# AMC_SATA_Adapter.net
KiCad netlist of a schematic drawn in Altium Designer
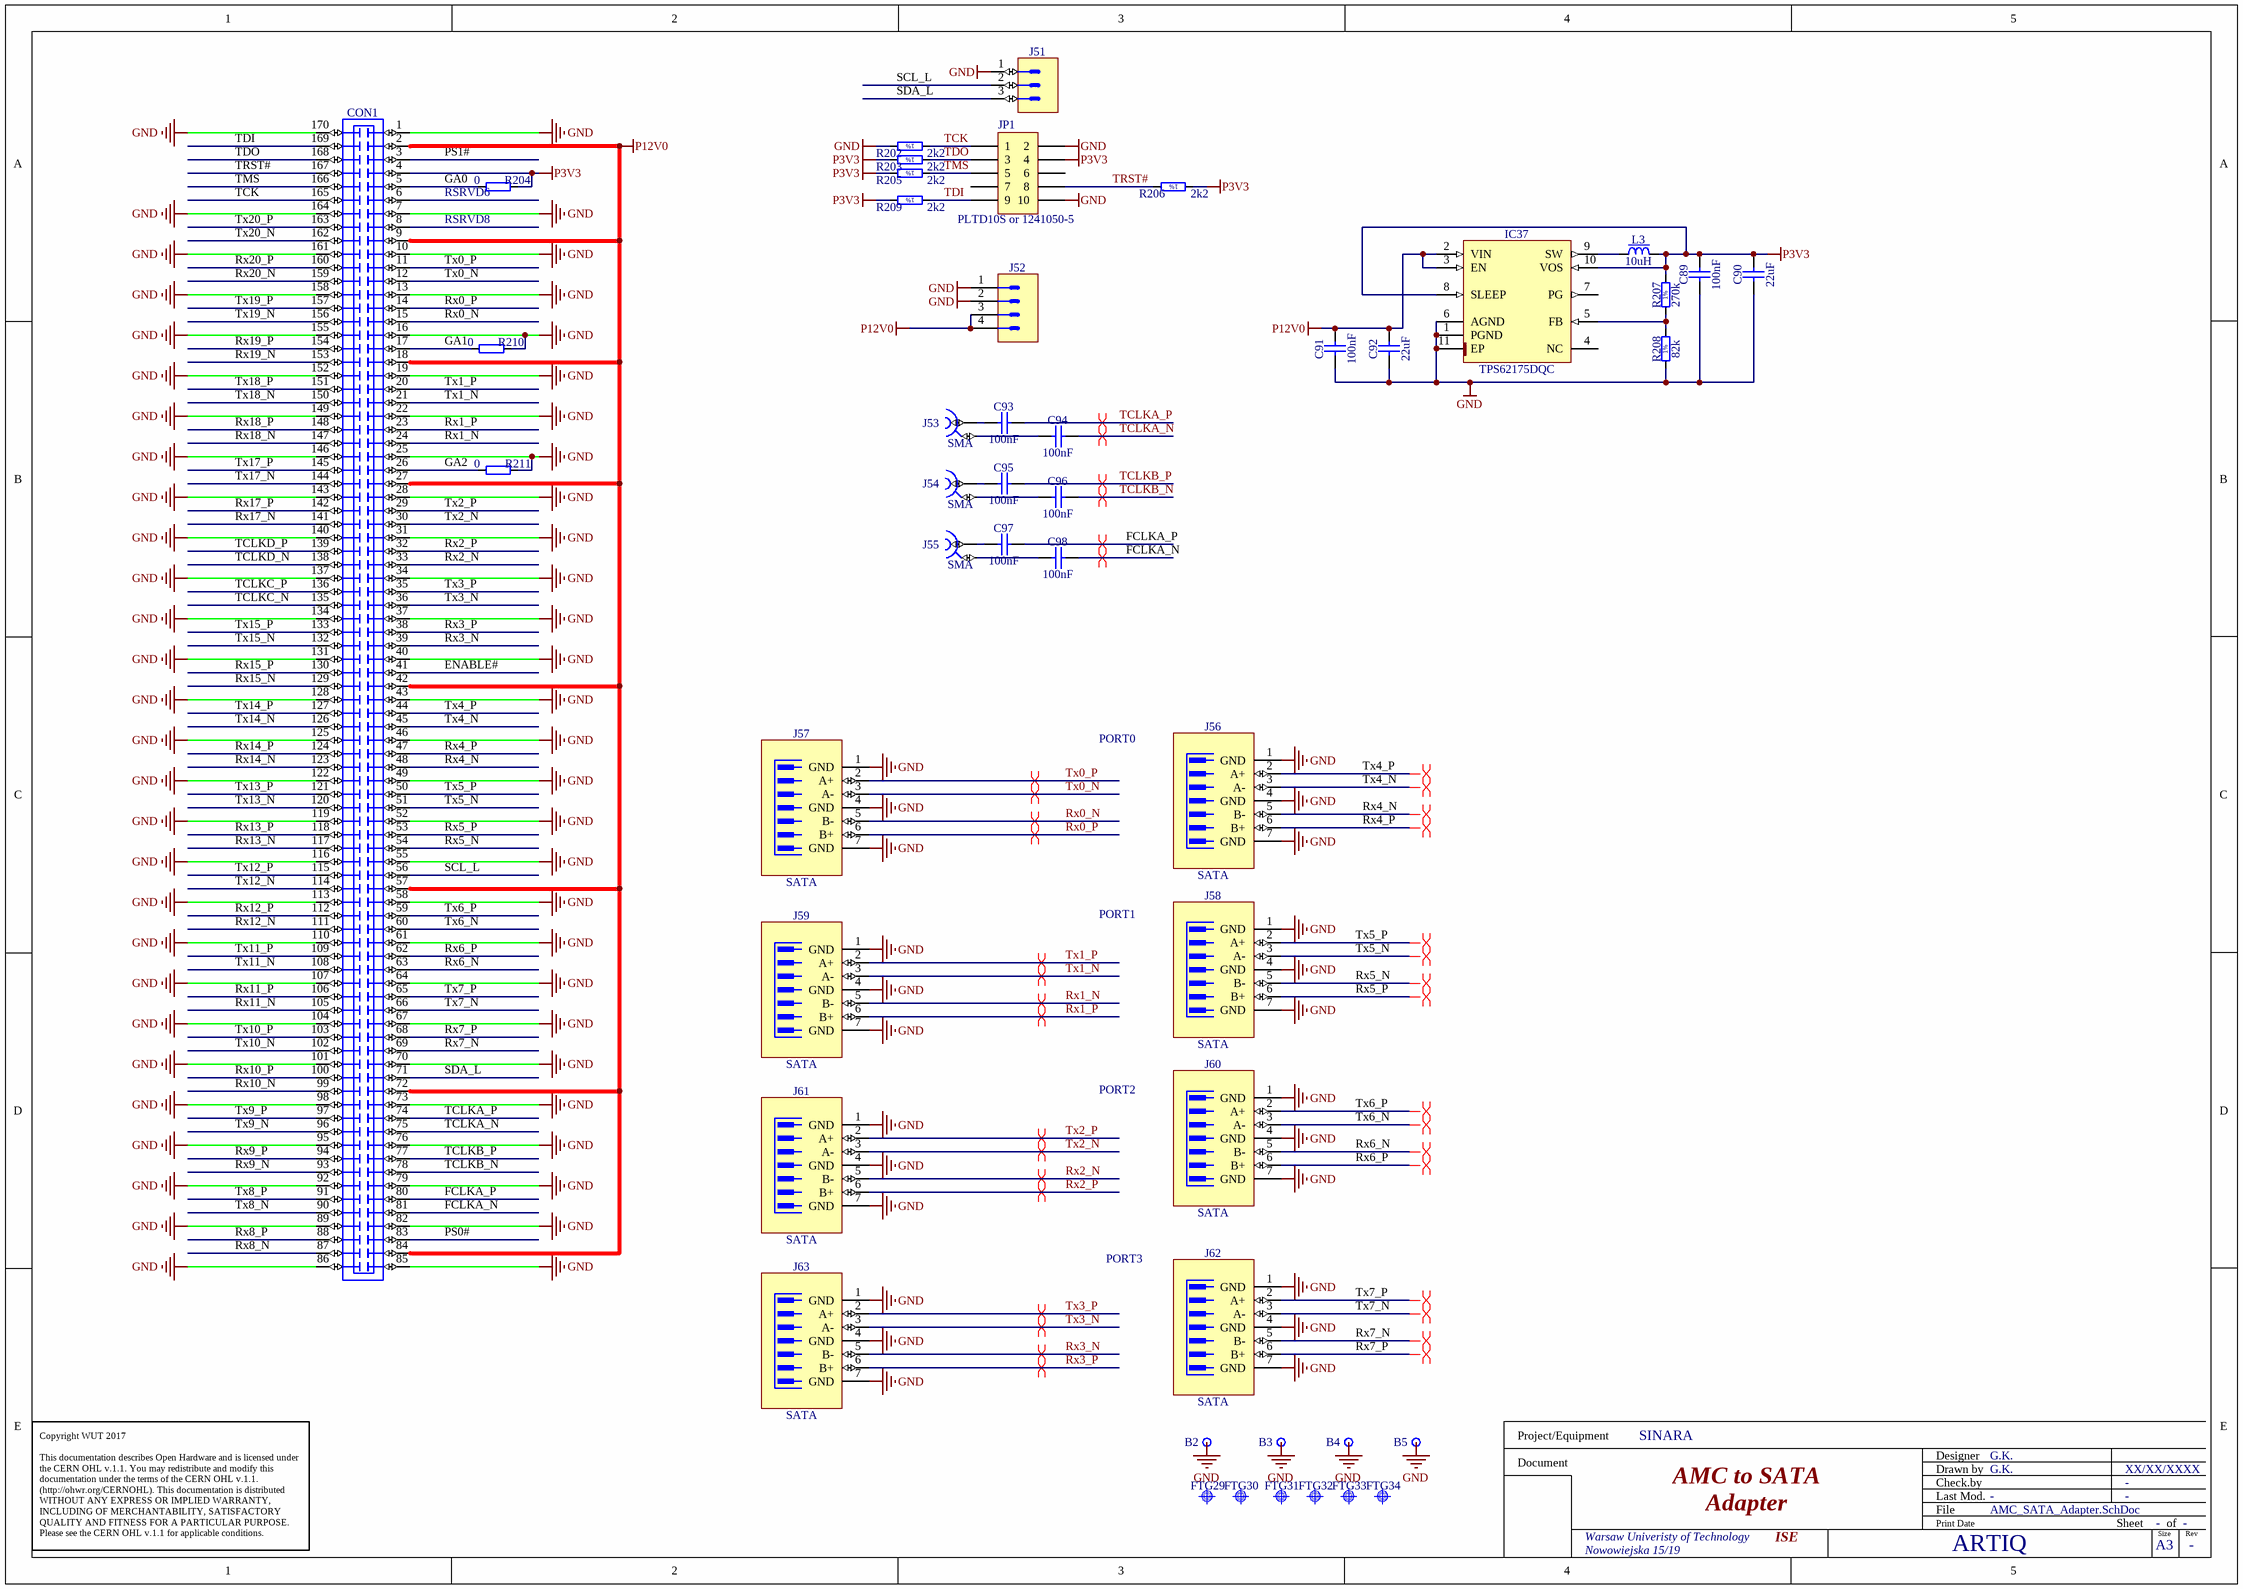
[diagram p0: AMC_SATA_Adapter.SchDoc]

(export (version "E")
  (design (tool "Eeschema 10.0.6"))
  (components
    (comp (ref "B2")
      (value "~")
      (footprint "MTG270_500")
      (description "Through Hole Pad")
      (libsource (lib "Pads") (part "Through Hole Pad"))
    )
    (comp (ref "B3")
      (value "~")
      (footprint "MTG270_500")
      (description "Through Hole Pad")
      (libsource (lib "Pads") (part "Through Hole Pad"))
    )
    (comp (ref "B4")
      (value "~")
      (footprint "MTG270_500")
      (description "Through Hole Pad")
      (libsource (lib "Pads") (part "Through Hole Pad"))
    )
    (comp (ref "B5")
      (value "~")
      (footprint "MTG270_500")
      (description "Through Hole Pad")
      (libsource (lib "Pads") (part "Through Hole Pad"))
    )
    (comp (ref "C89")
      (value "100nF")
      (footprint "CAPC1005X55N")
      (description "Non-polarised capacitor")
      (fields
        (field (name "PART NUMBER") "CC0402_100NF_16V_10%_X5R")
        (field (name "VOLTAGE") "16V")
        (field (name "AUTHOR") "CERN DEM JLC")
      )
      (libsource (lib "Capacitors") (part "Capacitor - non polarized"))
    )
    (comp (ref "C90")
      (value "22uF")
      (footprint "CAPC2012X135N")
      (description "Non-polarised capacitor")
      (fields
        (field (name "PART NUMBER") "CC0805_22UF_16V_10%_X5R")
        (field (name "VOLTAGE") "16V")
        (field (name "AUTHOR") "CERN DEM JLC")
      )
      (libsource (lib "Capacitors") (part "Capacitor - non polarized"))
    )
    (comp (ref "C91")
      (value "100nF")
      (footprint "CAPC1005X55N")
      (description "Non-polarised capacitor")
      (fields
        (field (name "PART NUMBER") "CC0402_100NF_16V_10%_X5R")
        (field (name "VOLTAGE") "16V")
        (field (name "AUTHOR") "CERN DEM JLC")
      )
      (libsource (lib "Capacitors") (part "Capacitor - non polarized"))
    )
    (comp (ref "C92")
      (value "22uF")
      (footprint "CAPC2012X135N")
      (description "Non-polarised capacitor")
      (fields
        (field (name "PART NUMBER") "CC0805_22UF_16V_10%_X5R")
        (field (name "VOLTAGE") "16V")
        (field (name "AUTHOR") "CERN DEM JLC")
      )
      (libsource (lib "Capacitors") (part "Capacitor - non polarized"))
    )
    (comp (ref "C93")
      (value "100nF")
      (footprint "CAPC0603X33N")
      (description "Non-polarised capacitor")
      (fields
        (field (name "PART NUMBER") "CC0201_100NF_6.3V_10%_X5R")
        (field (name "VOLTAGE") "6.3V")
        (field (name "AUTHOR") "CERN DEM JLC")
      )
      (libsource (lib "Capacitors") (part "Capacitor - non polarized"))
    )
    (comp (ref "C94")
      (value "100nF")
      (footprint "CAPC0603X33N")
      (description "Non-polarised capacitor")
      (fields
        (field (name "PART NUMBER") "CC0201_100NF_6.3V_10%_X5R")
        (field (name "VOLTAGE") "6.3V")
        (field (name "AUTHOR") "CERN DEM JLC")
      )
      (libsource (lib "Capacitors") (part "Capacitor - non polarized"))
    )
    (comp (ref "C95")
      (value "100nF")
      (footprint "CAPC0603X33N")
      (description "Non-polarised capacitor")
      (fields
        (field (name "PART NUMBER") "CC0201_100NF_6.3V_10%_X5R")
        (field (name "VOLTAGE") "6.3V")
        (field (name "AUTHOR") "CERN DEM JLC")
      )
      (libsource (lib "Capacitors") (part "Capacitor - non polarized"))
    )
    (comp (ref "C96")
      (value "100nF")
      (footprint "CAPC0603X33N")
      (description "Non-polarised capacitor")
      (fields
        (field (name "PART NUMBER") "CC0201_100NF_6.3V_10%_X5R")
        (field (name "VOLTAGE") "6.3V")
        (field (name "AUTHOR") "CERN DEM JLC")
      )
      (libsource (lib "Capacitors") (part "Capacitor - non polarized"))
    )
    (comp (ref "C97")
      (value "100nF")
      (footprint "CAPC0603X33N")
      (description "Non-polarised capacitor")
      (fields
        (field (name "PART NUMBER") "CC0201_100NF_6.3V_10%_X5R")
        (field (name "VOLTAGE") "6.3V")
        (field (name "AUTHOR") "CERN DEM JLC")
      )
      (libsource (lib "Capacitors") (part "Capacitor - non polarized"))
    )
    (comp (ref "C98")
      (value "100nF")
      (footprint "CAPC0603X33N")
      (description "Non-polarised capacitor")
      (fields
        (field (name "PART NUMBER") "CC0201_100NF_6.3V_10%_X5R")
        (field (name "VOLTAGE") "6.3V")
        (field (name "AUTHOR") "CERN DEM JLC")
      )
      (libsource (lib "Capacitors") (part "Capacitor - non polarized"))
    )
    (comp (ref "CON1")
      (value "SAMTEC_MTCA-085-02-S-DV-SMT-K-TR")
      (footprint "SAMTEC_MTCA-085-02-S-DV-SMT-K-TR")
      (description "170 Poles,  Micro TCA (Telecom Computing Architecture) Edge Card Socket")
      (fields
        (field (name "MANUFACTURER") "SAMTEC")
        (field (name "MANUFACTURER PART NUMBER") "MTCA-085-02-S-DV-SMT-K-TR")
        (field (name "AUTHOR") "CERN DEM JLC")
      )
      (libsource (lib "Connectors") (part "Micro TCA Female 170"))
    )
    (comp (ref "FTG29")
      (value "Use only in PCB")
      (description "Fiducial Target")
      (libsource (lib "Pads") (part "Fiducial Target"))
    )
    (comp (ref "FTG30")
      (value "Use only in PCB")
      (description "Fiducial Target")
      (libsource (lib "Pads") (part "Fiducial Target"))
    )
    (comp (ref "FTG31")
      (value "Use only in PCB")
      (description "Fiducial Target")
      (libsource (lib "Pads") (part "Fiducial Target"))
    )
    (comp (ref "FTG32")
      (value "Use only in PCB")
      (description "Fiducial Target")
      (libsource (lib "Pads") (part "Fiducial Target"))
    )
    (comp (ref "FTG33")
      (value "Use only in PCB")
      (description "Fiducial Target")
      (libsource (lib "Pads") (part "Fiducial Target"))
    )
    (comp (ref "FTG34")
      (value "Use only in PCB")
      (description "Fiducial Target")
      (libsource (lib "Pads") (part "Fiducial Target"))
    )
    (comp (ref "IC37")
      (value "TPS62175DQC")
      (footprint "SON50P200X300X80-11N-R94X250")
      (description "4.75-28VDC to 1-6VDC, 500mA Step-Down Converter With Sleep Mode")
      (fields (field (name "MANUFACTURER") "TEXAS INSTRUMENTS") (field (name "AUTHOR") "CERN DEM JMW"))
      (libsource (lib "ICs And Semiconductors") (part "TPS62175"))
    )
    (comp (ref "J51")
      (value "Header 3")
      (footprint "HARWIN_M22-2010305")
      (description "Connector 3 Male")
      (fields
        (field (name "PART NUMBER") "HARWIN_M22-2010305")
        (field (name "MANUFACTURER") "HARWIN")
        (field (name "AUTHOR") "CERN DEM JLC")
      )
      (libsource (lib "Connectors") (part "Connector 3 Male"))
    )
    (comp (ref "J52")
      (value "Mini-Fit Jr.™")
      (footprint "MOLEX_39-28-1043")
      (description "Connector 4 Male")
      (fields
        (field (name "PART NUMBER") "MOLEX_39-28-1043")
        (field (name "MANUFACTURER") "MOLEX")
        (field (name "AUTHOR") "CERN DEM JLC")
      )
      (libsource (lib "Connectors") (part "Connector 4 Male"))
    )
    (comp (ref "J53")
      (value "SMA")
      (footprint "HUBER-SUHNER_82_SMA-50-0-41/133_NE")
      (fields
        (field (name "PART NUMBER") "HUBER-SUHNER_82_SMA-50-0-41/133_NE")
        (field (name "MANUFACTURER") "HUBER+SUHNER")
        (field (name "MANUFACTURER PART NUMBER") "82_SMA-50-0-41/133_NE")
        (field (name "AUTHOR") "CERN DEM JLC")
      )
      (libsource (lib "Connectors") (part "Coax_1Female_1Shield"))
    )
    (comp (ref "J54")
      (value "SMA")
      (footprint "HUBER-SUHNER_82_SMA-50-0-41/133_NE")
      (fields
        (field (name "PART NUMBER") "HUBER-SUHNER_82_SMA-50-0-41/133_NE")
        (field (name "MANUFACTURER") "HUBER+SUHNER")
        (field (name "MANUFACTURER PART NUMBER") "82_SMA-50-0-41/133_NE")
        (field (name "AUTHOR") "CERN DEM JLC")
      )
      (libsource (lib "Connectors") (part "Coax_1Female_1Shield"))
    )
    (comp (ref "J55")
      (value "SMA")
      (footprint "HUBER-SUHNER_82_SMA-50-0-41/133_NE")
      (fields
        (field (name "PART NUMBER") "HUBER-SUHNER_82_SMA-50-0-41/133_NE")
        (field (name "MANUFACTURER") "HUBER+SUHNER")
        (field (name "MANUFACTURER PART NUMBER") "82_SMA-50-0-41/133_NE")
        (field (name "AUTHOR") "CERN DEM JLC")
      )
      (libsource (lib "Connectors") (part "Coax_1Female_1Shield"))
    )
    (comp (ref "J56")
      (value "SATA")
      (footprint "MOLEX_67800-5005")
      (description "7 Pin SATA Receptacle")
      (fields
        (field (name "PART NUMBER") "MOLEX_67800-5005")
        (field (name "MANUFACTURER") "MOLEX")
        (field (name "AUTHOR") "CERN DEM MR")
      )
      (libsource (lib "Connectors") (part "Connector SATA 7 Male"))
    )
    (comp (ref "J57")
      (value "SATA")
      (footprint "MOLEX_67800-5005")
      (description "7 Pin SATA Receptacle")
      (fields
        (field (name "PART NUMBER") "MOLEX_67800-5005")
        (field (name "MANUFACTURER") "MOLEX")
        (field (name "AUTHOR") "CERN DEM MR")
      )
      (libsource (lib "Connectors") (part "Connector SATA 7 Male"))
    )
    (comp (ref "J58")
      (value "SATA")
      (footprint "MOLEX_67800-5005")
      (description "7 Pin SATA Receptacle")
      (fields
        (field (name "PART NUMBER") "MOLEX_67800-5005")
        (field (name "MANUFACTURER") "MOLEX")
        (field (name "AUTHOR") "CERN DEM MR")
      )
      (libsource (lib "Connectors") (part "Connector SATA 7 Male"))
    )
    (comp (ref "J59")
      (value "SATA")
      (footprint "MOLEX_67800-5005")
      (description "7 Pin SATA Receptacle")
      (fields
        (field (name "PART NUMBER") "MOLEX_67800-5005")
        (field (name "MANUFACTURER") "MOLEX")
        (field (name "AUTHOR") "CERN DEM MR")
      )
      (libsource (lib "Connectors") (part "Connector SATA 7 Male"))
    )
    (comp (ref "J60")
      (value "SATA")
      (footprint "MOLEX_67800-5005")
      (description "7 Pin SATA Receptacle")
      (fields
        (field (name "PART NUMBER") "MOLEX_67800-5005")
        (field (name "MANUFACTURER") "MOLEX")
        (field (name "AUTHOR") "CERN DEM MR")
      )
      (libsource (lib "Connectors") (part "Connector SATA 7 Male"))
    )
    (comp (ref "J61")
      (value "SATA")
      (footprint "MOLEX_67800-5005")
      (description "7 Pin SATA Receptacle")
      (fields
        (field (name "PART NUMBER") "MOLEX_67800-5005")
        (field (name "MANUFACTURER") "MOLEX")
        (field (name "AUTHOR") "CERN DEM MR")
      )
      (libsource (lib "Connectors") (part "Connector SATA 7 Male"))
    )
    (comp (ref "J62")
      (value "SATA")
      (footprint "MOLEX_67800-5005")
      (description "7 Pin SATA Receptacle")
      (fields
        (field (name "PART NUMBER") "MOLEX_67800-5005")
        (field (name "MANUFACTURER") "MOLEX")
        (field (name "AUTHOR") "CERN DEM MR")
      )
      (libsource (lib "Connectors") (part "Connector SATA 7 Male"))
    )
    (comp (ref "J63")
      (value "SATA")
      (footprint "MOLEX_67800-5005")
      (description "7 Pin SATA Receptacle")
      (fields
        (field (name "PART NUMBER") "MOLEX_67800-5005")
        (field (name "MANUFACTURER") "MOLEX")
        (field (name "AUTHOR") "CERN DEM MR")
      )
      (libsource (lib "Connectors") (part "Connector SATA 7 Male"))
    )
    (comp (ref "JP1")
      (value "PLTD10S or 1241050-5")
      (footprint "PLTD10S")
      (description "Goldpin 2.54mm, male header")
      (libsource (lib "LIBRARY_SCH") (part "CON_2x5 2.54 male SMT"))
    )
    (comp (ref "L3")
      (value "10uH")
      (footprint "IND_MURATA-PS_8400")
      (description "Inductor With Core")
      (fields
        (field (name "PART NUMBER") "IND_10UH_10%_MURATA-PS_8400")
        (field (name "POWER") "950mA")
        (field (name "AUTHOR") "CERN DEM JLC")
      )
      (libsource (lib "Inductors & Transformers") (part "Inductor With Magnetic core"))
    )
    (comp (ref "R202")
      (value "2k2")
      (footprint "RESC1005X40N")
      (description "Resistor - 1%")
      (fields
        (field (name "PART NUMBER") "R0402_2K2_1%_0.0625W_100PPM")
        (field (name "POWER") "0.0625W")
        (field (name "AUTHOR") "CERN DEM JLC")
      )
      (libsource (lib "Resistors") (part "Resistor - 1%"))
    )
    (comp (ref "R203")
      (value "2k2")
      (footprint "RESC1005X40N")
      (description "Resistor - 1%")
      (fields
        (field (name "PART NUMBER") "R0402_2K2_1%_0.0625W_100PPM")
        (field (name "POWER") "0.0625W")
        (field (name "AUTHOR") "CERN DEM JLC")
      )
      (libsource (lib "Resistors") (part "Resistor - 1%"))
    )
    (comp (ref "R204")
      (value "0")
      (footprint "RESC1005X40N")
      (description "Resistor")
      (fields
        (field (name "PART NUMBER") "R0402_0R_JUMPER")
        (field (name "MANUFACTURER") "GENERIC")
        (field (name "AUTHOR") "CERN DEM JLC")
      )
      (libsource (lib "Resistors") (part "Resistor"))
    )
    (comp (ref "R205")
      (value "2k2")
      (footprint "RESC1005X40N")
      (description "Resistor - 1%")
      (fields
        (field (name "PART NUMBER") "R0402_2K2_1%_0.0625W_100PPM")
        (field (name "POWER") "0.0625W")
        (field (name "AUTHOR") "CERN DEM JLC")
      )
      (libsource (lib "Resistors") (part "Resistor - 1%"))
    )
    (comp (ref "R206")
      (value "2k2")
      (footprint "RESC1005X40N")
      (description "Resistor - 1%")
      (fields
        (field (name "PART NUMBER") "R0402_2K2_1%_0.0625W_100PPM")
        (field (name "POWER") "0.0625W")
        (field (name "AUTHOR") "CERN DEM JLC")
      )
      (libsource (lib "Resistors") (part "Resistor - 1%"))
    )
    (comp (ref "R207")
      (value "270k")
      (footprint "RESC1608X55N")
      (description "Resistor - 1%")
      (fields
        (field (name "PART NUMBER") "R0603_270K_1%_0.1W_100PPM")
        (field (name "POWER") "0.1W")
        (field (name "AUTHOR") "CERN DEM JLC")
      )
      (libsource (lib "Resistors") (part "Resistor - 1%"))
    )
    (comp (ref "R208")
      (value "82k")
      (footprint "RESC1608X55N")
      (description "Resistor - 1%")
      (fields
        (field (name "PART NUMBER") "R0603_82K_1%_0.1W_100PPM")
        (field (name "POWER") "0.1W")
        (field (name "AUTHOR") "CERN DEM JLC")
      )
      (libsource (lib "Resistors") (part "Resistor - 1%"))
    )
    (comp (ref "R209")
      (value "2k2")
      (footprint "RESC1005X40N")
      (description "Resistor - 1%")
      (fields
        (field (name "PART NUMBER") "R0402_2K2_1%_0.0625W_100PPM")
        (field (name "POWER") "0.0625W")
        (field (name "AUTHOR") "CERN DEM JLC")
      )
      (libsource (lib "Resistors") (part "Resistor - 1%"))
    )
    (comp (ref "R210")
      (value "0")
      (footprint "RESC1005X40N")
      (description "Resistor")
      (fields
        (field (name "PART NUMBER") "R0402_0R_JUMPER")
        (field (name "MANUFACTURER") "GENERIC")
        (field (name "AUTHOR") "CERN DEM JLC")
      )
      (libsource (lib "Resistors") (part "Resistor"))
    )
    (comp (ref "R211")
      (value "0")
      (footprint "RESC1005X40N")
      (description "Resistor")
      (fields
        (field (name "PART NUMBER") "R0402_0R_JUMPER")
        (field (name "MANUFACTURER") "GENERIC")
        (field (name "AUTHOR") "CERN DEM JLC")
      )
      (libsource (lib "Resistors") (part "Resistor"))
    )
  )
  (nets
    (net (code "1") (name "/ENABLE#") (class "Default")
      (node (ref "CON1") (pin "41") (pinfunction "41_41") (pintype "bidirectional"))
    )
    (net (code "2") (name "/FCLKA_N") (class "Default")
      (node (ref "C98") (pin "2") (pinfunction "2_2") (pintype "passive"))
      (node (ref "CON1") (pin "81") (pinfunction "81_81") (pintype "bidirectional"))
    )
    (net (code "3") (name "/FCLKA_P") (class "Default")
      (node (ref "C97") (pin "2") (pinfunction "2_2") (pintype "passive"))
      (node (ref "CON1") (pin "80") (pinfunction "80_80") (pintype "bidirectional"))
    )
    (net (code "4") (name "/GA0") (class "Default")
      (node (ref "CON1") (pin "5") (pinfunction "5_5") (pintype "bidirectional"))
      (node (ref "R204") (pin "1") (pinfunction "1_1") (pintype "passive"))
    )
    (net (code "5") (name "/GA1") (class "Default")
      (node (ref "CON1") (pin "17") (pinfunction "17_17") (pintype "bidirectional"))
      (node (ref "R210") (pin "1") (pinfunction "1_1") (pintype "passive"))
    )
    (net (code "6") (name "/GA2") (class "Default")
      (node (ref "CON1") (pin "26") (pinfunction "26_26") (pintype "bidirectional"))
      (node (ref "R211") (pin "1") (pinfunction "1_1") (pintype "passive"))
    )
    (net (code "7") (name "/PS0#") (class "Default")
      (node (ref "CON1") (pin "83") (pinfunction "83_83") (pintype "bidirectional"))
    )
    (net (code "8") (name "/PS1#") (class "Default")
      (node (ref "CON1") (pin "3") (pinfunction "3_3") (pintype "bidirectional"))
    )
    (net (code "9") (name "/Rx0_N") (class "Default")
      (node (ref "CON1") (pin "15") (pinfunction "15_15") (pintype "bidirectional"))
      (node (ref "J57") (pin "5") (pinfunction "B-_5") (pintype "bidirectional"))
    )
    (net (code "10") (name "/Rx0_P") (class "Default")
      (node (ref "CON1") (pin "14") (pinfunction "14_14") (pintype "bidirectional"))
      (node (ref "J57") (pin "6") (pinfunction "B+_6") (pintype "bidirectional"))
    )
    (net (code "11") (name "/Rx1_N") (class "Default")
      (node (ref "CON1") (pin "24") (pinfunction "24_24") (pintype "bidirectional"))
      (node (ref "J59") (pin "5") (pinfunction "B-_5") (pintype "bidirectional"))
    )
    (net (code "12") (name "/Rx1_P") (class "Default")
      (node (ref "CON1") (pin "23") (pinfunction "23_23") (pintype "bidirectional"))
      (node (ref "J59") (pin "6") (pinfunction "B+_6") (pintype "bidirectional"))
    )
    (net (code "13") (name "/Rx2_N") (class "Default")
      (node (ref "CON1") (pin "33") (pinfunction "33_33") (pintype "bidirectional"))
      (node (ref "J61") (pin "5") (pinfunction "B-_5") (pintype "bidirectional"))
    )
    (net (code "14") (name "/Rx2_P") (class "Default")
      (node (ref "CON1") (pin "32") (pinfunction "32_32") (pintype "bidirectional"))
      (node (ref "J61") (pin "6") (pinfunction "B+_6") (pintype "bidirectional"))
    )
    (net (code "15") (name "/Rx3_N") (class "Default")
      (node (ref "CON1") (pin "39") (pinfunction "39_39") (pintype "bidirectional"))
      (node (ref "J63") (pin "5") (pinfunction "B-_5") (pintype "bidirectional"))
    )
    (net (code "16") (name "/Rx3_P") (class "Default")
      (node (ref "CON1") (pin "38") (pinfunction "38_38") (pintype "bidirectional"))
      (node (ref "J63") (pin "6") (pinfunction "B+_6") (pintype "bidirectional"))
    )
    (net (code "17") (name "/Rx4_N") (class "Default")
      (node (ref "CON1") (pin "48") (pinfunction "48_48") (pintype "bidirectional"))
      (node (ref "J56") (pin "5") (pinfunction "B-_5") (pintype "bidirectional"))
    )
    (net (code "18") (name "/Rx4_P") (class "Default")
      (node (ref "CON1") (pin "47") (pinfunction "47_47") (pintype "bidirectional"))
      (node (ref "J56") (pin "6") (pinfunction "B+_6") (pintype "bidirectional"))
    )
    (net (code "19") (name "/Rx5_N") (class "Default")
      (node (ref "CON1") (pin "54") (pinfunction "54_54") (pintype "bidirectional"))
      (node (ref "J58") (pin "5") (pinfunction "B-_5") (pintype "bidirectional"))
    )
    (net (code "20") (name "/Rx5_P") (class "Default")
      (node (ref "CON1") (pin "53") (pinfunction "53_53") (pintype "bidirectional"))
      (node (ref "J58") (pin "6") (pinfunction "B+_6") (pintype "bidirectional"))
    )
    (net (code "21") (name "/Rx6_N") (class "Default")
      (node (ref "CON1") (pin "63") (pinfunction "63_63") (pintype "bidirectional"))
      (node (ref "J60") (pin "5") (pinfunction "B-_5") (pintype "bidirectional"))
    )
    (net (code "22") (name "/Rx6_P") (class "Default")
      (node (ref "CON1") (pin "62") (pinfunction "62_62") (pintype "bidirectional"))
      (node (ref "J60") (pin "6") (pinfunction "B+_6") (pintype "bidirectional"))
    )
    (net (code "23") (name "/Rx7_N") (class "Default")
      (node (ref "CON1") (pin "69") (pinfunction "69_69") (pintype "bidirectional"))
      (node (ref "J62") (pin "5") (pinfunction "B-_5") (pintype "bidirectional"))
    )
    (net (code "24") (name "/Rx7_P") (class "Default")
      (node (ref "CON1") (pin "68") (pinfunction "68_68") (pintype "bidirectional"))
      (node (ref "J62") (pin "6") (pinfunction "B+_6") (pintype "bidirectional"))
    )
    (net (code "25") (name "/Rx8_N") (class "Default")
      (node (ref "CON1") (pin "87") (pinfunction "87_87") (pintype "bidirectional"))
    )
    (net (code "26") (name "/Rx8_P") (class "Default")
      (node (ref "CON1") (pin "88") (pinfunction "88_88") (pintype "bidirectional"))
    )
    (net (code "27") (name "/Rx9_N") (class "Default")
      (node (ref "CON1") (pin "93") (pinfunction "93_93") (pintype "bidirectional"))
    )
    (net (code "28") (name "/Rx9_P") (class "Default")
      (node (ref "CON1") (pin "94") (pinfunction "94_94") (pintype "bidirectional"))
    )
    (net (code "29") (name "/Rx10_N") (class "Default")
      (node (ref "CON1") (pin "99") (pinfunction "99_99") (pintype "bidirectional"))
    )
    (net (code "30") (name "/Rx10_P") (class "Default")
      (node (ref "CON1") (pin "100") (pinfunction "100_100") (pintype "bidirectional"))
    )
    (net (code "31") (name "/Rx11_N") (class "Default")
      (node (ref "CON1") (pin "105") (pinfunction "105_105") (pintype "bidirectional"))
    )
    (net (code "32") (name "/Rx11_P") (class "Default")
      (node (ref "CON1") (pin "106") (pinfunction "106_106") (pintype "bidirectional"))
    )
    (net (code "33") (name "/Rx12_N") (class "Default")
      (node (ref "CON1") (pin "111") (pinfunction "111_111") (pintype "bidirectional"))
    )
    (net (code "34") (name "/Rx12_P") (class "Default")
      (node (ref "CON1") (pin "112") (pinfunction "112_112") (pintype "bidirectional"))
    )
    (net (code "35") (name "/Rx13_N") (class "Default")
      (node (ref "CON1") (pin "117") (pinfunction "117_117") (pintype "bidirectional"))
    )
    (net (code "36") (name "/Rx13_P") (class "Default")
      (node (ref "CON1") (pin "118") (pinfunction "118_118") (pintype "bidirectional"))
    )
    (net (code "37") (name "/Rx14_N") (class "Default")
      (node (ref "CON1") (pin "123") (pinfunction "123_123") (pintype "bidirectional"))
    )
    (net (code "38") (name "/Rx14_P") (class "Default")
      (node (ref "CON1") (pin "124") (pinfunction "124_124") (pintype "bidirectional"))
    )
    (net (code "39") (name "/Rx15_N") (class "Default")
      (node (ref "CON1") (pin "129") (pinfunction "129_129") (pintype "bidirectional"))
    )
    (net (code "40") (name "/Rx15_P") (class "Default")
      (node (ref "CON1") (pin "130") (pinfunction "130_130") (pintype "bidirectional"))
    )
    (net (code "41") (name "/Rx17_N") (class "Default")
      (node (ref "CON1") (pin "141") (pinfunction "141_141") (pintype "bidirectional"))
    )
    (net (code "42") (name "/Rx17_P") (class "Default")
      (node (ref "CON1") (pin "142") (pinfunction "142_142") (pintype "bidirectional"))
    )
    (net (code "43") (name "/Rx18_N") (class "Default")
      (node (ref "CON1") (pin "147") (pinfunction "147_147") (pintype "bidirectional"))
    )
    (net (code "44") (name "/Rx18_P") (class "Default")
      (node (ref "CON1") (pin "148") (pinfunction "148_148") (pintype "bidirectional"))
    )
    (net (code "45") (name "/Rx19_N") (class "Default")
      (node (ref "CON1") (pin "153") (pinfunction "153_153") (pintype "bidirectional"))
    )
    (net (code "46") (name "/Rx19_P") (class "Default")
      (node (ref "CON1") (pin "154") (pinfunction "154_154") (pintype "bidirectional"))
    )
    (net (code "47") (name "/Rx20_N") (class "Default")
      (node (ref "CON1") (pin "159") (pinfunction "159_159") (pintype "bidirectional"))
    )
    (net (code "48") (name "/Rx20_P") (class "Default")
      (node (ref "CON1") (pin "160") (pinfunction "160_160") (pintype "bidirectional"))
    )
    (net (code "49") (name "/SCL_L") (class "Default")
      (node (ref "CON1") (pin "56") (pinfunction "56_56") (pintype "bidirectional"))
      (node (ref "J51") (pin "2") (pinfunction "2_2") (pintype "bidirectional"))
    )
    (net (code "50") (name "/SDA_L") (class "Default")
      (node (ref "CON1") (pin "71") (pinfunction "71_71") (pintype "bidirectional"))
      (node (ref "J51") (pin "3") (pinfunction "3_3") (pintype "bidirectional"))
    )
    (net (code "51") (name "/TCK") (class "Default")
      (node (ref "CON1") (pin "165") (pinfunction "165_165") (pintype "bidirectional"))
      (node (ref "JP1") (pin "1") (pinfunction "1_1") (pintype "passive"))
      (node (ref "R202") (pin "1") (pinfunction "1_1") (pintype "passive"))
    )
    (net (code "52") (name "/TCLKA_N") (class "Default")
      (node (ref "C94") (pin "2") (pinfunction "2_2") (pintype "passive"))
      (node (ref "CON1") (pin "75") (pinfunction "75_75") (pintype "bidirectional"))
    )
    (net (code "53") (name "/TCLKA_P") (class "Default")
      (node (ref "C93") (pin "2") (pinfunction "2_2") (pintype "passive"))
      (node (ref "CON1") (pin "74") (pinfunction "74_74") (pintype "bidirectional"))
    )
    (net (code "54") (name "/TCLKB_N") (class "Default")
      (node (ref "C96") (pin "2") (pinfunction "2_2") (pintype "passive"))
      (node (ref "CON1") (pin "78") (pinfunction "78_78") (pintype "bidirectional"))
    )
    (net (code "55") (name "/TCLKB_P") (class "Default")
      (node (ref "C95") (pin "2") (pinfunction "2_2") (pintype "passive"))
      (node (ref "CON1") (pin "77") (pinfunction "77_77") (pintype "bidirectional"))
    )
    (net (code "56") (name "/TCLKC_N") (class "Default")
      (node (ref "CON1") (pin "135") (pinfunction "135_135") (pintype "bidirectional"))
    )
    (net (code "57") (name "/TCLKC_P") (class "Default")
      (node (ref "CON1") (pin "136") (pinfunction "136_136") (pintype "bidirectional"))
    )
    (net (code "58") (name "/TCLKD_N") (class "Default")
      (node (ref "CON1") (pin "138") (pinfunction "138_138") (pintype "bidirectional"))
    )
    (net (code "59") (name "/TCLKD_P") (class "Default")
      (node (ref "CON1") (pin "139") (pinfunction "139_139") (pintype "bidirectional"))
    )
    (net (code "60") (name "/TDI") (class "Default")
      (node (ref "CON1") (pin "169") (pinfunction "169_169") (pintype "bidirectional"))
      (node (ref "JP1") (pin "9") (pinfunction "9_9") (pintype "passive"))
      (node (ref "R209") (pin "1") (pinfunction "1_1") (pintype "passive"))
    )
    (net (code "61") (name "/TDO") (class "Default")
      (node (ref "CON1") (pin "168") (pinfunction "168_168") (pintype "bidirectional"))
      (node (ref "JP1") (pin "3") (pinfunction "3_3") (pintype "passive"))
      (node (ref "R203") (pin "1") (pinfunction "1_1") (pintype "passive"))
    )
    (net (code "62") (name "/TMS") (class "Default")
      (node (ref "CON1") (pin "166") (pinfunction "166_166") (pintype "bidirectional"))
      (node (ref "JP1") (pin "5") (pinfunction "5_5") (pintype "passive"))
      (node (ref "R205") (pin "1") (pinfunction "1_1") (pintype "passive"))
    )
    (net (code "63") (name "/TRST#") (class "Default")
      (node (ref "CON1") (pin "167") (pinfunction "167_167") (pintype "bidirectional"))
      (node (ref "JP1") (pin "8") (pinfunction "8_8") (pintype "passive"))
      (node (ref "R206") (pin "2") (pinfunction "2_2") (pintype "passive"))
    )
    (net (code "64") (name "/Tx0_N") (class "Default")
      (node (ref "CON1") (pin "12") (pinfunction "12_12") (pintype "bidirectional"))
      (node (ref "J57") (pin "3") (pinfunction "A-_3") (pintype "bidirectional"))
    )
    (net (code "65") (name "/Tx0_P") (class "Default")
      (node (ref "CON1") (pin "11") (pinfunction "11_11") (pintype "bidirectional"))
      (node (ref "J57") (pin "2") (pinfunction "A+_2") (pintype "bidirectional"))
    )
    (net (code "66") (name "/Tx1_N") (class "Default")
      (node (ref "CON1") (pin "21") (pinfunction "21_21") (pintype "bidirectional"))
      (node (ref "J59") (pin "3") (pinfunction "A-_3") (pintype "bidirectional"))
    )
    (net (code "67") (name "/Tx1_P") (class "Default")
      (node (ref "CON1") (pin "20") (pinfunction "20_20") (pintype "bidirectional"))
      (node (ref "J59") (pin "2") (pinfunction "A+_2") (pintype "bidirectional"))
    )
    (net (code "68") (name "/Tx2_N") (class "Default")
      (node (ref "CON1") (pin "30") (pinfunction "30_30") (pintype "bidirectional"))
      (node (ref "J61") (pin "3") (pinfunction "A-_3") (pintype "bidirectional"))
    )
    (net (code "69") (name "/Tx2_P") (class "Default")
      (node (ref "CON1") (pin "29") (pinfunction "29_29") (pintype "bidirectional"))
      (node (ref "J61") (pin "2") (pinfunction "A+_2") (pintype "bidirectional"))
    )
    (net (code "70") (name "/Tx3_N") (class "Default")
      (node (ref "CON1") (pin "36") (pinfunction "36_36") (pintype "bidirectional"))
      (node (ref "J63") (pin "3") (pinfunction "A-_3") (pintype "bidirectional"))
    )
    (net (code "71") (name "/Tx3_P") (class "Default")
      (node (ref "CON1") (pin "35") (pinfunction "35_35") (pintype "bidirectional"))
      (node (ref "J63") (pin "2") (pinfunction "A+_2") (pintype "bidirectional"))
    )
    (net (code "72") (name "/Tx4_N") (class "Default")
      (node (ref "CON1") (pin "45") (pinfunction "45_45") (pintype "bidirectional"))
      (node (ref "J56") (pin "3") (pinfunction "A-_3") (pintype "bidirectional"))
    )
    (net (code "73") (name "/Tx4_P") (class "Default")
      (node (ref "CON1") (pin "44") (pinfunction "44_44") (pintype "bidirectional"))
      (node (ref "J56") (pin "2") (pinfunction "A+_2") (pintype "bidirectional"))
    )
    (net (code "74") (name "/Tx5_N") (class "Default")
      (node (ref "CON1") (pin "51") (pinfunction "51_51") (pintype "bidirectional"))
      (node (ref "J58") (pin "3") (pinfunction "A-_3") (pintype "bidirectional"))
    )
    (net (code "75") (name "/Tx5_P") (class "Default")
      (node (ref "CON1") (pin "50") (pinfunction "50_50") (pintype "bidirectional"))
      (node (ref "J58") (pin "2") (pinfunction "A+_2") (pintype "bidirectional"))
    )
    (net (code "76") (name "/Tx6_N") (class "Default")
      (node (ref "CON1") (pin "60") (pinfunction "60_60") (pintype "bidirectional"))
      (node (ref "J60") (pin "3") (pinfunction "A-_3") (pintype "bidirectional"))
    )
    (net (code "77") (name "/Tx6_P") (class "Default")
      (node (ref "CON1") (pin "59") (pinfunction "59_59") (pintype "bidirectional"))
      (node (ref "J60") (pin "2") (pinfunction "A+_2") (pintype "bidirectional"))
    )
    (net (code "78") (name "/Tx7_N") (class "Default")
      (node (ref "CON1") (pin "66") (pinfunction "66_66") (pintype "bidirectional"))
      (node (ref "J62") (pin "3") (pinfunction "A-_3") (pintype "bidirectional"))
    )
    (net (code "79") (name "/Tx7_P") (class "Default")
      (node (ref "CON1") (pin "65") (pinfunction "65_65") (pintype "bidirectional"))
      (node (ref "J62") (pin "2") (pinfunction "A+_2") (pintype "bidirectional"))
    )
    (net (code "80") (name "/Tx8_N") (class "Default")
      (node (ref "CON1") (pin "90") (pinfunction "90_90") (pintype "bidirectional"))
    )
    (net (code "81") (name "/Tx8_P") (class "Default")
      (node (ref "CON1") (pin "91") (pinfunction "91_91") (pintype "bidirectional"))
    )
    (net (code "82") (name "/Tx9_N") (class "Default")
      (node (ref "CON1") (pin "96") (pinfunction "96_96") (pintype "bidirectional"))
    )
    (net (code "83") (name "/Tx9_P") (class "Default")
      (node (ref "CON1") (pin "97") (pinfunction "97_97") (pintype "bidirectional"))
    )
    (net (code "84") (name "/Tx10_N") (class "Default")
      (node (ref "CON1") (pin "102") (pinfunction "102_102") (pintype "bidirectional"))
    )
    (net (code "85") (name "/Tx10_P") (class "Default")
      (node (ref "CON1") (pin "103") (pinfunction "103_103") (pintype "bidirectional"))
    )
    (net (code "86") (name "/Tx11_N") (class "Default")
      (node (ref "CON1") (pin "108") (pinfunction "108_108") (pintype "bidirectional"))
    )
    (net (code "87") (name "/Tx11_P") (class "Default")
      (node (ref "CON1") (pin "109") (pinfunction "109_109") (pintype "bidirectional"))
    )
    (net (code "88") (name "/Tx12_N") (class "Default")
      (node (ref "CON1") (pin "114") (pinfunction "114_114") (pintype "bidirectional"))
    )
    (net (code "89") (name "/Tx12_P") (class "Default")
      (node (ref "CON1") (pin "115") (pinfunction "115_115") (pintype "bidirectional"))
    )
    (net (code "90") (name "/Tx13_N") (class "Default")
      (node (ref "CON1") (pin "120") (pinfunction "120_120") (pintype "bidirectional"))
    )
    (net (code "91") (name "/Tx13_P") (class "Default")
      (node (ref "CON1") (pin "121") (pinfunction "121_121") (pintype "bidirectional"))
    )
    (net (code "92") (name "/Tx14_N") (class "Default")
      (node (ref "CON1") (pin "126") (pinfunction "126_126") (pintype "bidirectional"))
    )
    (net (code "93") (name "/Tx14_P") (class "Default")
      (node (ref "CON1") (pin "127") (pinfunction "127_127") (pintype "bidirectional"))
    )
    (net (code "94") (name "/Tx15_N") (class "Default")
      (node (ref "CON1") (pin "132") (pinfunction "132_132") (pintype "bidirectional"))
    )
    (net (code "95") (name "/Tx15_P") (class "Default")
      (node (ref "CON1") (pin "133") (pinfunction "133_133") (pintype "bidirectional"))
    )
    (net (code "96") (name "/Tx17_N") (class "Default")
      (node (ref "CON1") (pin "144") (pinfunction "144_144") (pintype "bidirectional"))
    )
    (net (code "97") (name "/Tx17_P") (class "Default")
      (node (ref "CON1") (pin "145") (pinfunction "145_145") (pintype "bidirectional"))
    )
    (net (code "98") (name "/Tx18_N") (class "Default")
      (node (ref "CON1") (pin "150") (pinfunction "150_150") (pintype "bidirectional"))
    )
    (net (code "99") (name "/Tx18_P") (class "Default")
      (node (ref "CON1") (pin "151") (pinfunction "151_151") (pintype "bidirectional"))
    )
    (net (code "100") (name "/Tx19_N") (class "Default")
      (node (ref "CON1") (pin "156") (pinfunction "156_156") (pintype "bidirectional"))
    )
    (net (code "101") (name "/Tx19_P") (class "Default")
      (node (ref "CON1") (pin "157") (pinfunction "157_157") (pintype "bidirectional"))
    )
    (net (code "102") (name "/Tx20_N") (class "Default")
      (node (ref "CON1") (pin "162") (pinfunction "162_162") (pintype "bidirectional"))
    )
    (net (code "103") (name "/Tx20_P") (class "Default")
      (node (ref "CON1") (pin "163") (pinfunction "163_163") (pintype "bidirectional"))
    )
    (net (code "104") (name "GND") (class "Default")
      (node (ref "B2") (pin "1") (pinfunction "1_1") (pintype "bidirectional"))
      (node (ref "B3") (pin "1") (pinfunction "1_1") (pintype "bidirectional"))
      (node (ref "B4") (pin "1") (pinfunction "1_1") (pintype "bidirectional"))
      (node (ref "B5") (pin "1") (pinfunction "1_1") (pintype "bidirectional"))
      (node (ref "C89") (pin "1") (pinfunction "1_1") (pintype "passive"))
      (node (ref "C90") (pin "1") (pinfunction "1_1") (pintype "passive"))
      (node (ref "C91") (pin "1") (pinfunction "1_1") (pintype "passive"))
      (node (ref "C92") (pin "1") (pinfunction "1_1") (pintype "passive"))
      (node (ref "CON1") (pin "1") (pinfunction "1_1") (pintype "bidirectional"))
      (node (ref "CON1") (pin "10") (pinfunction "10_10") (pintype "bidirectional"))
      (node (ref "CON1") (pin "101") (pinfunction "101_101") (pintype "bidirectional"))
      (node (ref "CON1") (pin "104") (pinfunction "104_104") (pintype "bidirectional"))
      (node (ref "CON1") (pin "107") (pinfunction "107_107") (pintype "bidirectional"))
      (node (ref "CON1") (pin "110") (pinfunction "110_110") (pintype "bidirectional"))
      (node (ref "CON1") (pin "113") (pinfunction "113_113") (pintype "bidirectional"))
      (node (ref "CON1") (pin "116") (pinfunction "116_116") (pintype "bidirectional"))
      (node (ref "CON1") (pin "119") (pinfunction "119_119") (pintype "bidirectional"))
      (node (ref "CON1") (pin "122") (pinfunction "122_122") (pintype "bidirectional"))
      (node (ref "CON1") (pin "125") (pinfunction "125_125") (pintype "bidirectional"))
      (node (ref "CON1") (pin "128") (pinfunction "128_128") (pintype "bidirectional"))
      (node (ref "CON1") (pin "13") (pinfunction "13_13") (pintype "bidirectional"))
      (node (ref "CON1") (pin "131") (pinfunction "131_131") (pintype "bidirectional"))
      (node (ref "CON1") (pin "134") (pinfunction "134_134") (pintype "bidirectional"))
      (node (ref "CON1") (pin "137") (pinfunction "137_137") (pintype "bidirectional"))
      (node (ref "CON1") (pin "140") (pinfunction "140_140") (pintype "bidirectional"))
      (node (ref "CON1") (pin "143") (pinfunction "143_143") (pintype "bidirectional"))
      (node (ref "CON1") (pin "146") (pinfunction "146_146") (pintype "bidirectional"))
      (node (ref "CON1") (pin "149") (pinfunction "149_149") (pintype "bidirectional"))
      (node (ref "CON1") (pin "152") (pinfunction "152_152") (pintype "bidirectional"))
      (node (ref "CON1") (pin "155") (pinfunction "155_155") (pintype "bidirectional"))
      (node (ref "CON1") (pin "158") (pinfunction "158_158") (pintype "bidirectional"))
      (node (ref "CON1") (pin "16") (pinfunction "16_16") (pintype "bidirectional"))
      (node (ref "CON1") (pin "161") (pinfunction "161_161") (pintype "bidirectional"))
      (node (ref "CON1") (pin "164") (pinfunction "164_164") (pintype "bidirectional"))
      (node (ref "CON1") (pin "170") (pinfunction "170_170") (pintype "bidirectional"))
      (node (ref "CON1") (pin "19") (pinfunction "19_19") (pintype "bidirectional"))
      (node (ref "CON1") (pin "22") (pinfunction "22_22") (pintype "bidirectional"))
      (node (ref "CON1") (pin "25") (pinfunction "25_25") (pintype "bidirectional"))
      (node (ref "CON1") (pin "28") (pinfunction "28_28") (pintype "bidirectional"))
      (node (ref "CON1") (pin "31") (pinfunction "31_31") (pintype "bidirectional"))
      (node (ref "CON1") (pin "34") (pinfunction "34_34") (pintype "bidirectional"))
      (node (ref "CON1") (pin "37") (pinfunction "37_37") (pintype "bidirectional"))
      (node (ref "CON1") (pin "40") (pinfunction "40_40") (pintype "bidirectional"))
      (node (ref "CON1") (pin "43") (pinfunction "43_43") (pintype "bidirectional"))
      (node (ref "CON1") (pin "46") (pinfunction "46_46") (pintype "bidirectional"))
      (node (ref "CON1") (pin "49") (pinfunction "49_49") (pintype "bidirectional"))
      (node (ref "CON1") (pin "52") (pinfunction "52_52") (pintype "bidirectional"))
      (node (ref "CON1") (pin "55") (pinfunction "55_55") (pintype "bidirectional"))
      (node (ref "CON1") (pin "58") (pinfunction "58_58") (pintype "bidirectional"))
      (node (ref "CON1") (pin "61") (pinfunction "61_61") (pintype "bidirectional"))
      (node (ref "CON1") (pin "64") (pinfunction "64_64") (pintype "bidirectional"))
      (node (ref "CON1") (pin "67") (pinfunction "67_67") (pintype "bidirectional"))
      (node (ref "CON1") (pin "7") (pinfunction "7_7") (pintype "bidirectional"))
      (node (ref "CON1") (pin "70") (pinfunction "70_70") (pintype "bidirectional"))
      (node (ref "CON1") (pin "73") (pinfunction "73_73") (pintype "bidirectional"))
      (node (ref "CON1") (pin "76") (pinfunction "76_76") (pintype "bidirectional"))
      (node (ref "CON1") (pin "79") (pinfunction "79_79") (pintype "bidirectional"))
      (node (ref "CON1") (pin "82") (pinfunction "82_82") (pintype "bidirectional"))
      (node (ref "CON1") (pin "85") (pinfunction "85_85") (pintype "bidirectional"))
      (node (ref "CON1") (pin "86") (pinfunction "86_86") (pintype "bidirectional"))
      (node (ref "CON1") (pin "89") (pinfunction "89_89") (pintype "bidirectional"))
      (node (ref "CON1") (pin "92") (pinfunction "92_92") (pintype "bidirectional"))
      (node (ref "CON1") (pin "95") (pinfunction "95_95") (pintype "bidirectional"))
      (node (ref "CON1") (pin "98") (pinfunction "98_98") (pintype "bidirectional"))
      (node (ref "IC37") (pin "1") (pinfunction "PGND_1") (pintype "power_in"))
      (node (ref "IC37") (pin "11") (pinfunction "EP_11") (pintype "power_in"))
      (node (ref "IC37") (pin "6") (pinfunction "AGND_6") (pintype "power_in"))
      (node (ref "J51") (pin "1") (pinfunction "1_1") (pintype "bidirectional"))
      (node (ref "J52") (pin "1") (pinfunction "1_1") (pintype "passive"))
      (node (ref "J52") (pin "2") (pinfunction "2_2") (pintype "passive"))
      (node (ref "J56") (pin "1") (pinfunction "GND_1") (pintype "power_in"))
      (node (ref "J56") (pin "4") (pinfunction "GND_4") (pintype "power_in"))
      (node (ref "J56") (pin "7") (pinfunction "GND_7") (pintype "power_in"))
      (node (ref "J57") (pin "1") (pinfunction "GND_1") (pintype "power_in"))
      (node (ref "J57") (pin "4") (pinfunction "GND_4") (pintype "power_in"))
      (node (ref "J57") (pin "7") (pinfunction "GND_7") (pintype "power_in"))
      (node (ref "J58") (pin "1") (pinfunction "GND_1") (pintype "power_in"))
      (node (ref "J58") (pin "4") (pinfunction "GND_4") (pintype "power_in"))
      (node (ref "J58") (pin "7") (pinfunction "GND_7") (pintype "power_in"))
      (node (ref "J59") (pin "1") (pinfunction "GND_1") (pintype "power_in"))
      (node (ref "J59") (pin "4") (pinfunction "GND_4") (pintype "power_in"))
      (node (ref "J59") (pin "7") (pinfunction "GND_7") (pintype "power_in"))
      (node (ref "J60") (pin "1") (pinfunction "GND_1") (pintype "power_in"))
      (node (ref "J60") (pin "4") (pinfunction "GND_4") (pintype "power_in"))
      (node (ref "J60") (pin "7") (pinfunction "GND_7") (pintype "power_in"))
      (node (ref "J61") (pin "1") (pinfunction "GND_1") (pintype "power_in"))
      (node (ref "J61") (pin "4") (pinfunction "GND_4") (pintype "power_in"))
      (node (ref "J61") (pin "7") (pinfunction "GND_7") (pintype "power_in"))
      (node (ref "J62") (pin "1") (pinfunction "GND_1") (pintype "power_in"))
      (node (ref "J62") (pin "4") (pinfunction "GND_4") (pintype "power_in"))
      (node (ref "J62") (pin "7") (pinfunction "GND_7") (pintype "power_in"))
      (node (ref "J63") (pin "1") (pinfunction "GND_1") (pintype "power_in"))
      (node (ref "J63") (pin "4") (pinfunction "GND_4") (pintype "power_in"))
      (node (ref "J63") (pin "7") (pinfunction "GND_7") (pintype "power_in"))
      (node (ref "JP1") (pin "10") (pinfunction "10_10") (pintype "passive"))
      (node (ref "JP1") (pin "2") (pinfunction "2_2") (pintype "passive"))
      (node (ref "R202") (pin "2") (pinfunction "2_2") (pintype "passive"))
      (node (ref "R208") (pin "1") (pinfunction "1_1") (pintype "passive"))
      (node (ref "R210") (pin "2") (pinfunction "2_2") (pintype "passive"))
      (node (ref "R211") (pin "2") (pinfunction "2_2") (pintype "passive"))
    )
    (net (code "105") (name "Net-(C93-Pad1)") (class "Default")
      (node (ref "C93") (pin "1") (pinfunction "1_1") (pintype "passive"))
      (node (ref "J53") (pin "1") (pinfunction "1_1") (pintype "bidirectional"))
    )
    (net (code "106") (name "Net-(C94-Pad1)") (class "Default")
      (node (ref "C94") (pin "1") (pinfunction "1_1") (pintype "passive"))
      (node (ref "J53") (pin "2") (pinfunction "2_2") (pintype "bidirectional"))
    )
    (net (code "107") (name "Net-(C95-Pad1)") (class "Default")
      (node (ref "C95") (pin "1") (pinfunction "1_1") (pintype "passive"))
      (node (ref "J54") (pin "1") (pinfunction "1_1") (pintype "bidirectional"))
    )
    (net (code "108") (name "Net-(C96-Pad1)") (class "Default")
      (node (ref "C96") (pin "1") (pinfunction "1_1") (pintype "passive"))
      (node (ref "J54") (pin "2") (pinfunction "2_2") (pintype "bidirectional"))
    )
    (net (code "109") (name "Net-(C97-Pad1)") (class "Default")
      (node (ref "C97") (pin "1") (pinfunction "1_1") (pintype "passive"))
      (node (ref "J55") (pin "1") (pinfunction "1_1") (pintype "bidirectional"))
    )
    (net (code "110") (name "Net-(C98-Pad1)") (class "Default")
      (node (ref "C98") (pin "1") (pinfunction "1_1") (pintype "passive"))
      (node (ref "J55") (pin "2") (pinfunction "2_2") (pintype "bidirectional"))
    )
    (net (code "111") (name "Net-(IC37-FB)") (class "Default")
      (node (ref "IC37") (pin "5") (pinfunction "FB_5") (pintype "input"))
      (node (ref "R207") (pin "1") (pinfunction "1_1") (pintype "passive"))
      (node (ref "R208") (pin "2") (pinfunction "2_2") (pintype "passive"))
    )
    (net (code "112") (name "Net-(IC37-SW)") (class "Default")
      (node (ref "IC37") (pin "9") (pinfunction "SW_9") (pintype "output"))
      (node (ref "L3") (pin "1") (pinfunction "1_1") (pintype "passive"))
    )
    (net (code "113") (name "P3V3") (class "Default")
      (node (ref "C89") (pin "2") (pinfunction "2_2") (pintype "passive"))
      (node (ref "C90") (pin "2") (pinfunction "2_2") (pintype "passive"))
      (node (ref "CON1") (pin "4") (pinfunction "4_4") (pintype "bidirectional"))
      (node (ref "IC37") (pin "10") (pinfunction "VOS_10") (pintype "input"))
      (node (ref "IC37") (pin "8") (pinfunction "SLEEP_8") (pintype "input"))
      (node (ref "JP1") (pin "4") (pinfunction "4_4") (pintype "passive"))
      (node (ref "L3") (pin "2") (pinfunction "2_2") (pintype "passive"))
      (node (ref "R203") (pin "2") (pinfunction "2_2") (pintype "passive"))
      (node (ref "R204") (pin "2") (pinfunction "2_2") (pintype "passive"))
      (node (ref "R205") (pin "2") (pinfunction "2_2") (pintype "passive"))
      (node (ref "R206") (pin "1") (pinfunction "1_1") (pintype "passive"))
      (node (ref "R207") (pin "2") (pinfunction "2_2") (pintype "passive"))
      (node (ref "R209") (pin "2") (pinfunction "2_2") (pintype "passive"))
    )
    (net (code "114") (name "P12V0") (class "Default")
      (node (ref "C91") (pin "2") (pinfunction "2_2") (pintype "passive"))
      (node (ref "C92") (pin "2") (pinfunction "2_2") (pintype "passive"))
      (node (ref "CON1") (pin "18") (pinfunction "18_18") (pintype "bidirectional"))
      (node (ref "CON1") (pin "2") (pinfunction "2_2") (pintype "bidirectional"))
      (node (ref "CON1") (pin "27") (pinfunction "27_27") (pintype "bidirectional"))
      (node (ref "CON1") (pin "42") (pinfunction "42_42") (pintype "bidirectional"))
      (node (ref "CON1") (pin "57") (pinfunction "57_57") (pintype "bidirectional"))
      (node (ref "CON1") (pin "72") (pinfunction "72_72") (pintype "bidirectional"))
      (node (ref "CON1") (pin "84") (pinfunction "84_84") (pintype "bidirectional"))
      (node (ref "CON1") (pin "9") (pinfunction "9_9") (pintype "bidirectional"))
      (node (ref "IC37") (pin "2") (pinfunction "VIN_2") (pintype "input"))
      (node (ref "IC37") (pin "3") (pinfunction "EN_3") (pintype "input"))
      (node (ref "J52") (pin "3") (pinfunction "3_3") (pintype "passive"))
      (node (ref "J52") (pin "4") (pinfunction "4_4") (pintype "passive"))
    )
    (net (code "115") (name "unconnected-(CON1-Pad6)") (class "Default")
      (node (ref "CON1") (pin "6") (pinfunction "6_6") (pintype "bidirectional"))
    )
    (net (code "116") (name "unconnected-(CON1-Pad8)") (class "Default")
      (node (ref "CON1") (pin "8") (pinfunction "8_8") (pintype "bidirectional"))
    )
    (net (code "117") (name "unconnected-(IC37-NC-Pad4)") (class "Default")
      (node (ref "IC37") (pin "4") (pinfunction "NC_4") (pintype "passive"))
    )
    (net (code "118") (name "unconnected-(IC37-PG-Pad7)") (class "Default")
      (node (ref "IC37") (pin "7") (pinfunction "PG_7") (pintype "output"))
    )
    (net (code "119") (name "unconnected-(JP1-Pad6)") (class "Default")
      (node (ref "JP1") (pin "6") (pinfunction "6_6") (pintype "passive"))
    )
    (net (code "120") (name "unconnected-(JP1-Pad7)") (class "Default")
      (node (ref "JP1") (pin "7") (pinfunction "7_7") (pintype "passive"))
    )
  )
)
